# KQ_rfid_reader.net
KiCad netlist of a schematic drawn in EasyEDA
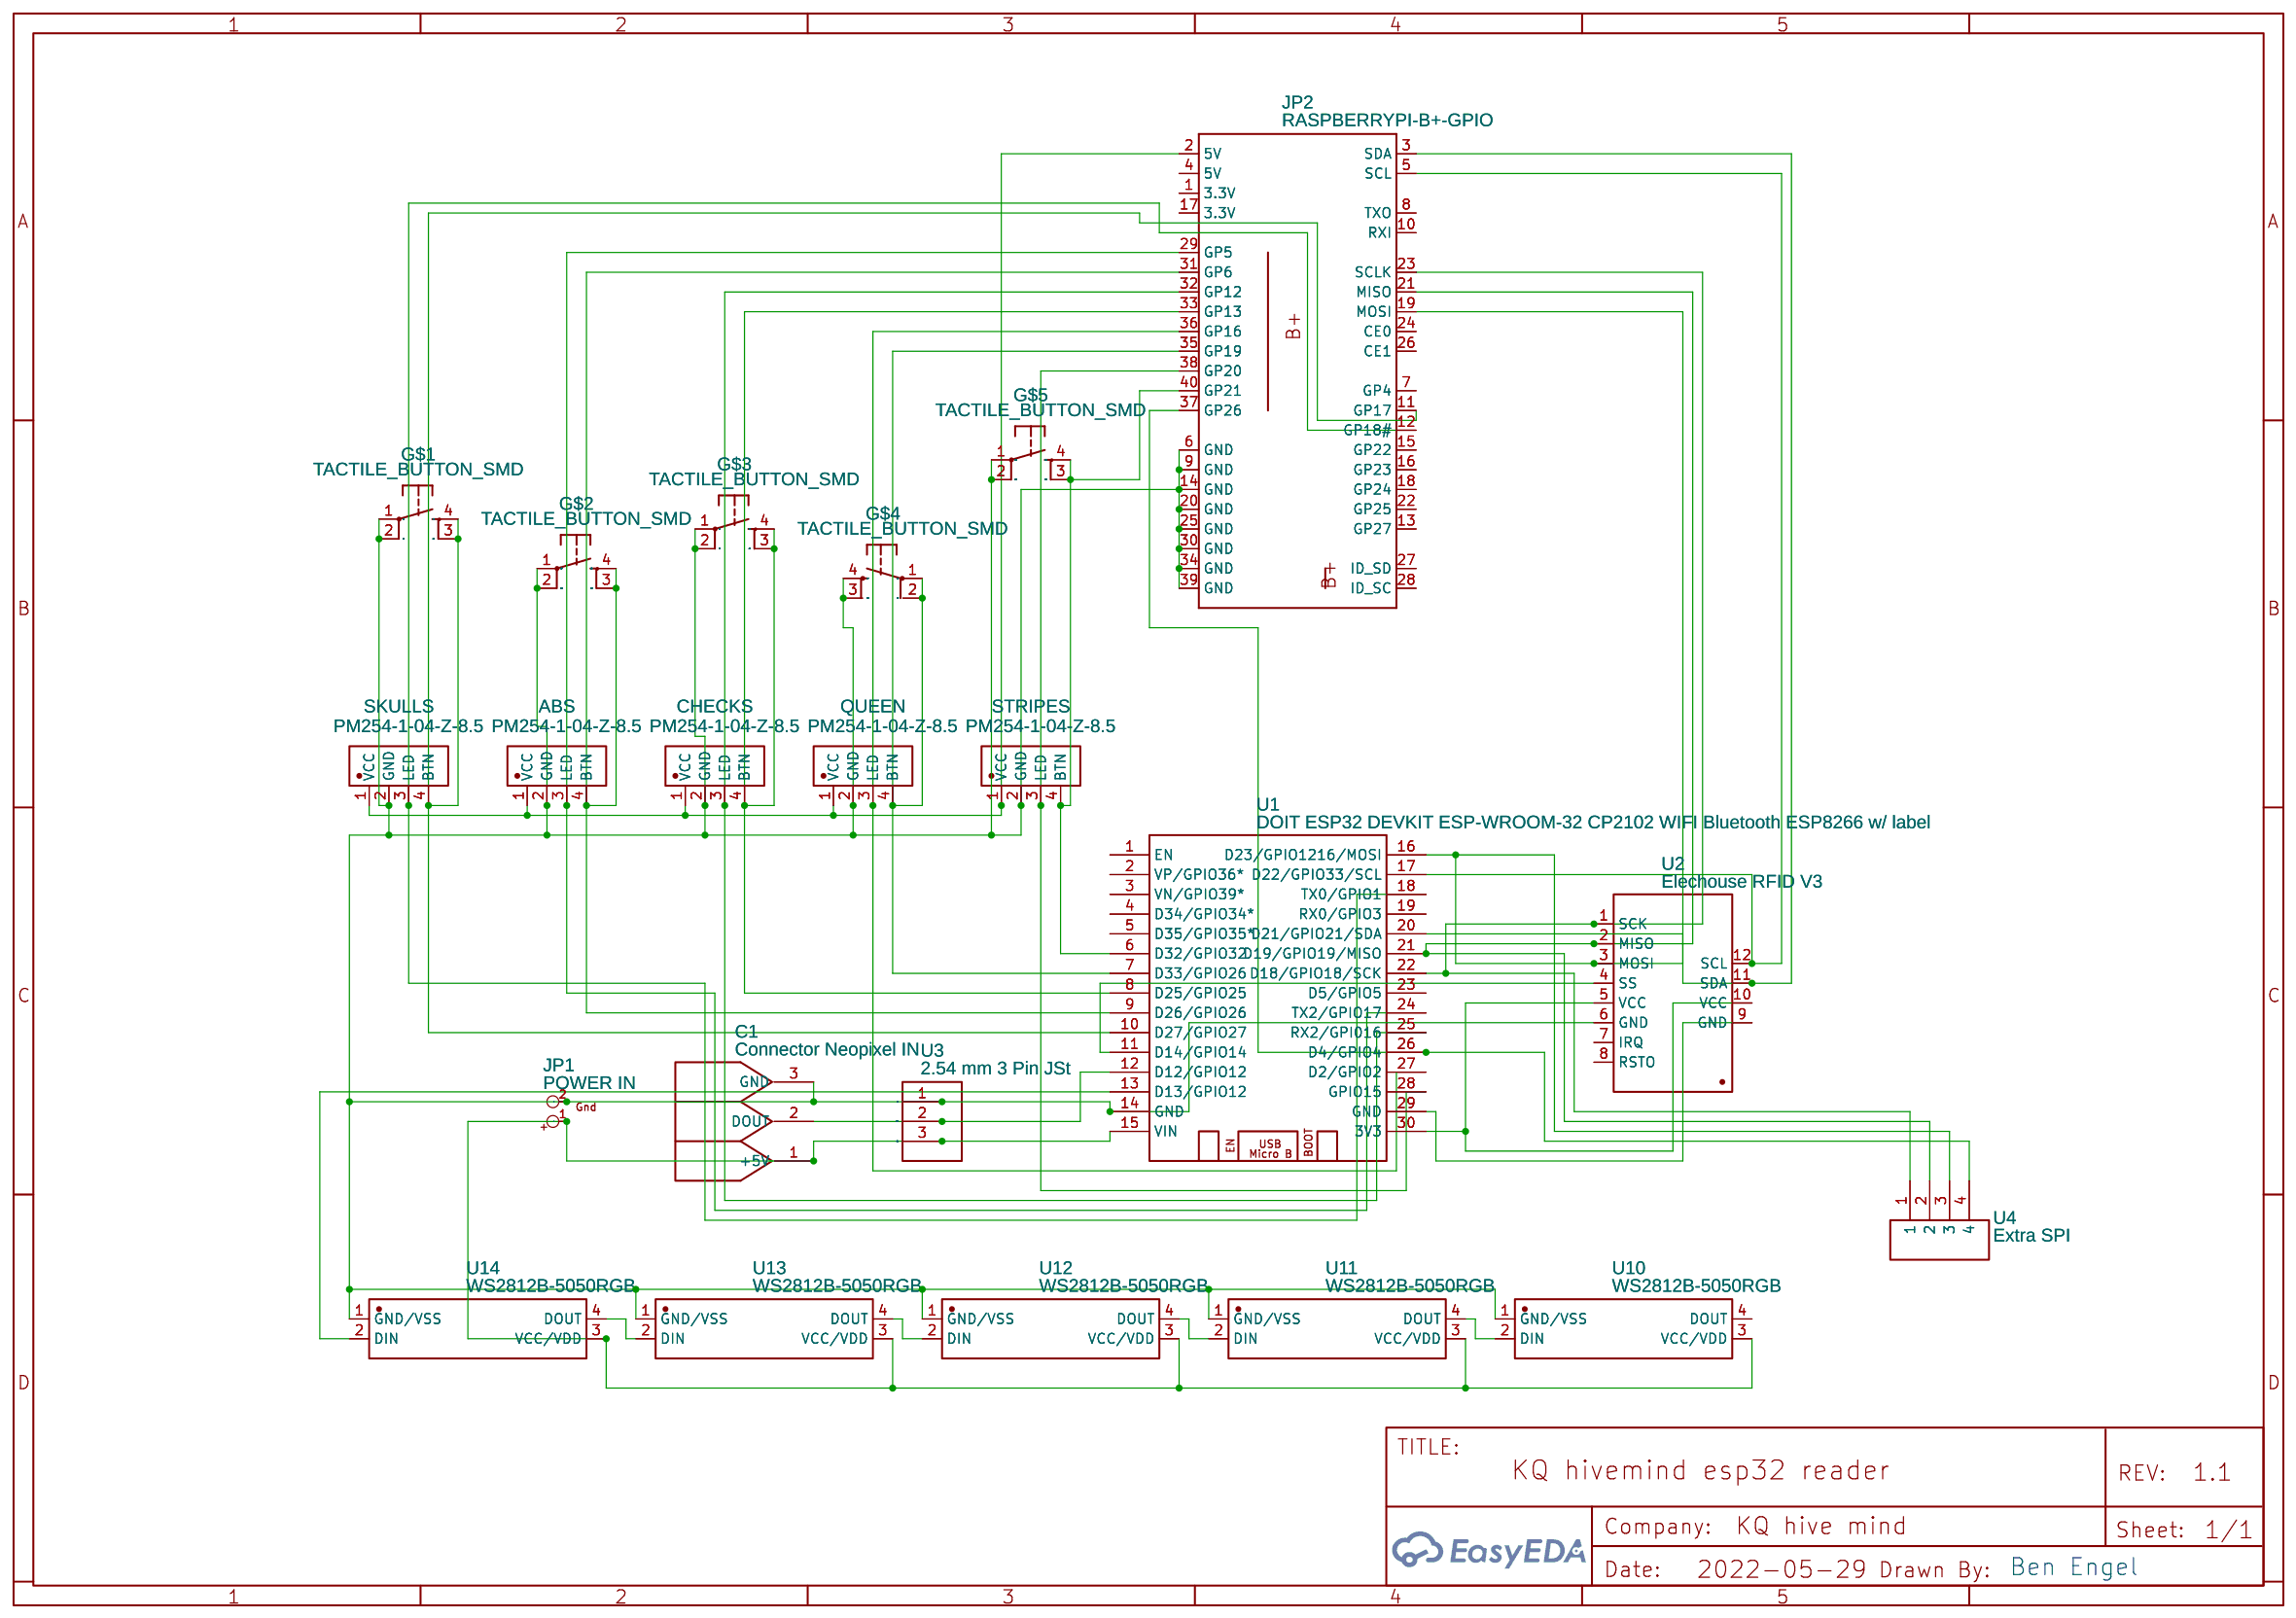
[diagram p0: schematic sheet]

(export (version "E")
  (design (tool "Eeschema 10.0.6"))
  (components
    (comp (ref "ABS")
      (value "PM254-1-04-Z-8.5")
      (fields (field (name "BOM_Supplier Part") "C2897367"))
      (libsource (lib "") (part "PM254-1-04-Z-8.5"))
    )
    (comp (ref "C1") (value "Connector Neopixel IN") (libsource (lib "") (part "Connector Neopixel IN")))
    (comp (ref "CHECKS")
      (value "PM254-1-04-Z-8.5")
      (fields (field (name "BOM_Supplier Part") "C2897367"))
      (libsource (lib "") (part "PM254-1-04-Z-8.5_1"))
    )
    (comp (ref "G$1") (value "TACTILE_BUTTON_SMD") (libsource (lib "") (part "TACTILE_BUTTON_SMD")))
    (comp (ref "G$2") (value "TACTILE_BUTTON_SMD") (libsource (lib "") (part "TACTILE_BUTTON_SMD")))
    (comp (ref "G$3") (value "TACTILE_BUTTON_SMD") (libsource (lib "") (part "TACTILE_BUTTON_SMD")))
    (comp (ref "G$4") (value "TACTILE_BUTTON_SMD") (libsource (lib "") (part "TACTILE_BUTTON_SMD_1")))
    (comp (ref "G$5") (value "TACTILE_BUTTON_SMD") (libsource (lib "") (part "TACTILE_BUTTON_SMD")))
    (comp (ref "JP1") (value "POWER IN") (libsource (lib "") (part "POWER IN")))
    (comp (ref "JP2") (value "RASPBERRYPI-B+-GPIO") (libsource (lib "") (part "RASPBERRYPI-B+-GPIO")))
    (comp (ref "QUEEN")
      (value "PM254-1-04-Z-8.5")
      (fields (field (name "BOM_Supplier Part") "C2897367"))
      (libsource (lib "") (part "PM254-1-04-Z-8.5_3"))
    )
    (comp (ref "SKULLS")
      (value "PM254-1-04-Z-8.5")
      (fields (field (name "BOM_Supplier Part") "C2897367"))
      (libsource (lib "") (part "PM254-1-04-Z-8.5_4"))
    )
    (comp (ref "STRIPES")
      (value "PM254-1-04-Z-8.5")
      (fields (field (name "BOM_Supplier Part") "C2897367"))
      (libsource (lib "") (part "PM254-1-04-Z-8.5_2"))
    )
    (comp (ref "U1")
      (value "DOIT ESP32 DEVKIT ESP-WROOM-32 CP2102 WIFI Bluetooth ESP8266 w/ label")
      (libsource (lib "") (part "DOIT ESP32 DEVKIT ESP-WROOM-32 CP2102 WIFI Bluetooth ESP8266 w/ label"))
    )
    (comp (ref "U2") (value "Elechouse RFID V3") (libsource (lib "") (part "Elechouse RFID V3")))
    (comp (ref "U3") (value "2.54 mm 3 Pin JSt") (libsource (lib "") (part "2.54 mm 3 Pin JSt")))
    (comp (ref "U4")
      (value "Extra SPI")
      (fields (field (name "BOM_Manufacturer Part") "1x2 Pin Header"))
      (libsource (lib "") (part "1X4 PIN HEADER"))
    )
    (comp (ref "U10")
      (value "WS2812B-5050RGB")
      (fields (field (name "BOM_Supplier Part") "C2838584"))
      (libsource (lib "") (part "WS2812B-5050RGB"))
    )
    (comp (ref "U11")
      (value "WS2812B-5050RGB")
      (fields (field (name "BOM_Supplier Part") "C2838584"))
      (libsource (lib "") (part "WS2812B-5050RGB"))
    )
    (comp (ref "U12")
      (value "WS2812B-5050RGB")
      (fields (field (name "BOM_Supplier Part") "C2838584"))
      (libsource (lib "") (part "WS2812B-5050RGB"))
    )
    (comp (ref "U13")
      (value "WS2812B-5050RGB")
      (fields (field (name "BOM_Supplier Part") "C2838584"))
      (libsource (lib "") (part "WS2812B-5050RGB"))
    )
    (comp (ref "U14")
      (value "WS2812B-5050RGB")
      (fields (field (name "BOM_Supplier Part") "C2838584"))
      (libsource (lib "") (part "WS2812B-5050RGB"))
    )
  )
  (nets
    (net (code "1") (name "Net-(ABS-BTN)") (class "Default")
      (node (ref "ABS") (pin "4") (pinfunction "BTN_4") (pintype "unspecified"))
      (node (ref "G$2") (pin "3") (pinfunction "SWB2_3") (pintype "bidirectional"))
      (node (ref "G$2") (pin "4") (pinfunction "SWA2_4") (pintype "bidirectional"))
      (node (ref "JP2") (pin "31") (pinfunction "GP6_31") (pintype "unspecified"))
      (node (ref "U1") (pin "9") (pinfunction "D26/GPIO26_9") (pintype "bidirectional"))
    )
    (net (code "2") (name "Net-(ABS-GND)") (class "Default")
      (node (ref "ABS") (pin "2") (pinfunction "GND_2") (pintype "unspecified"))
      (node (ref "C1") (pin "3") (pinfunction "GND_3") (pintype "unspecified"))
      (node (ref "CHECKS") (pin "2") (pinfunction "GND_2") (pintype "unspecified"))
      (node (ref "G$1") (pin "1") (pinfunction "SWA1_1") (pintype "bidirectional"))
      (node (ref "G$1") (pin "2") (pinfunction "SWB1_2") (pintype "bidirectional"))
      (node (ref "G$2") (pin "1") (pinfunction "SWA1_1") (pintype "bidirectional"))
      (node (ref "G$2") (pin "2") (pinfunction "SWB1_2") (pintype "bidirectional"))
      (node (ref "G$3") (pin "1") (pinfunction "SWA1_1") (pintype "bidirectional"))
      (node (ref "G$3") (pin "2") (pinfunction "SWB1_2") (pintype "bidirectional"))
      (node (ref "G$4") (pin "3") (pinfunction "SWB2_3") (pintype "bidirectional"))
      (node (ref "G$4") (pin "4") (pinfunction "SWA2_4") (pintype "bidirectional"))
      (node (ref "G$5") (pin "1") (pinfunction "SWA1_1") (pintype "bidirectional"))
      (node (ref "G$5") (pin "2") (pinfunction "SWB1_2") (pintype "bidirectional"))
      (node (ref "JP1") (pin "2") (pinfunction "-_2") (pintype "unspecified"))
      (node (ref "JP2") (pin "14") (pinfunction "GND_14") (pintype "passive"))
      (node (ref "JP2") (pin "20") (pinfunction "GND_20") (pintype "passive"))
      (node (ref "JP2") (pin "25") (pinfunction "GND_25") (pintype "passive"))
      (node (ref "JP2") (pin "30") (pinfunction "GND_30") (pintype "passive"))
      (node (ref "JP2") (pin "34") (pinfunction "GND_34") (pintype "passive"))
      (node (ref "JP2") (pin "39") (pinfunction "GND_39") (pintype "passive"))
      (node (ref "JP2") (pin "6") (pinfunction "GND_6") (pintype "passive"))
      (node (ref "JP2") (pin "9") (pinfunction "GND_9") (pintype "passive"))
      (node (ref "QUEEN") (pin "2") (pinfunction "GND_2") (pintype "unspecified"))
      (node (ref "SKULLS") (pin "2") (pinfunction "GND_2") (pintype "unspecified"))
      (node (ref "STRIPES") (pin "2") (pinfunction "GND_2") (pintype "unspecified"))
      (node (ref "U1") (pin "14") (pinfunction "GND_14") (pintype "bidirectional"))
      (node (ref "U10") (pin "1") (pinfunction "GND/VSS_1") (pintype "unspecified"))
      (node (ref "U11") (pin "1") (pinfunction "GND/VSS_1") (pintype "unspecified"))
      (node (ref "U12") (pin "1") (pinfunction "GND/VSS_1") (pintype "unspecified"))
      (node (ref "U13") (pin "1") (pinfunction "GND/VSS_1") (pintype "unspecified"))
      (node (ref "U14") (pin "1") (pinfunction "GND/VSS_1") (pintype "unspecified"))
      (node (ref "U2") (pin "6") (pinfunction "GND_6") (pintype "unspecified"))
      (node (ref "U3") (pin "1") (pinfunction "PIN_1") (pintype "unspecified"))
    )
    (net (code "3") (name "Net-(ABS-LED)") (class "Default")
      (node (ref "ABS") (pin "3") (pinfunction "LED_3") (pintype "unspecified"))
      (node (ref "JP2") (pin "29") (pinfunction "GP5_29") (pintype "unspecified"))
      (node (ref "U1") (pin "24") (pinfunction "TX2/GPIO17_24") (pintype "bidirectional"))
    )
    (net (code "4") (name "Net-(ABS-VCC)") (class "Default")
      (node (ref "ABS") (pin "1") (pinfunction "VCC_1") (pintype "unspecified"))
      (node (ref "CHECKS") (pin "1") (pinfunction "VCC_1") (pintype "unspecified"))
      (node (ref "JP2") (pin "2") (pinfunction "5V_2") (pintype "passive"))
      (node (ref "QUEEN") (pin "1") (pinfunction "VCC_1") (pintype "unspecified"))
      (node (ref "SKULLS") (pin "1") (pinfunction "VCC_1") (pintype "unspecified"))
      (node (ref "STRIPES") (pin "1") (pinfunction "VCC_1") (pintype "unspecified"))
    )
    (net (code "5") (name "Net-(C1-+5V)") (class "Default")
      (node (ref "C1") (pin "1") (pinfunction "+5V_1") (pintype "unspecified"))
      (node (ref "JP1") (pin "1") (pinfunction "+_1") (pintype "unspecified"))
      (node (ref "U1") (pin "15") (pinfunction "VIN_15") (pintype "input"))
      (node (ref "U10") (pin "3") (pinfunction "VCC/VDD_3") (pintype "unspecified"))
      (node (ref "U11") (pin "3") (pinfunction "VCC/VDD_3") (pintype "unspecified"))
      (node (ref "U12") (pin "3") (pinfunction "VCC/VDD_3") (pintype "unspecified"))
      (node (ref "U13") (pin "3") (pinfunction "VCC/VDD_3") (pintype "unspecified"))
      (node (ref "U14") (pin "3") (pinfunction "VCC/VDD_3") (pintype "unspecified"))
      (node (ref "U3") (pin "3") (pinfunction "OUTER_3") (pintype "unspecified"))
    )
    (net (code "6") (name "Net-(C1-DOUT)") (class "Default")
      (node (ref "C1") (pin "2") (pinfunction "DOUT_2") (pintype "unspecified"))
      (node (ref "U1") (pin "12") (pinfunction "D12/GPIO12_12") (pintype "bidirectional"))
      (node (ref "U3") (pin "2") (pinfunction "SWITCH_2") (pintype "unspecified"))
    )
    (net (code "7") (name "Net-(CHECKS-BTN)") (class "Default")
      (node (ref "CHECKS") (pin "4") (pinfunction "BTN_4") (pintype "unspecified"))
      (node (ref "G$3") (pin "3") (pinfunction "SWB2_3") (pintype "bidirectional"))
      (node (ref "G$3") (pin "4") (pinfunction "SWA2_4") (pintype "bidirectional"))
      (node (ref "JP2") (pin "33") (pinfunction "GP13_33") (pintype "unspecified"))
      (node (ref "U1") (pin "8") (pinfunction "D25/GPIO25_8") (pintype "bidirectional"))
    )
    (net (code "8") (name "Net-(CHECKS-LED)") (class "Default")
      (node (ref "CHECKS") (pin "3") (pinfunction "LED_3") (pintype "unspecified"))
      (node (ref "JP2") (pin "32") (pinfunction "GP12_32") (pintype "unspecified"))
      (node (ref "U1") (pin "25") (pinfunction "RX2/GPI016_25") (pintype "bidirectional"))
    )
    (net (code "9") (name "Net-(G$1-SWA2)") (class "Default")
      (node (ref "G$1") (pin "3") (pinfunction "SWB2_3") (pintype "bidirectional"))
      (node (ref "G$1") (pin "4") (pinfunction "SWA2_4") (pintype "bidirectional"))
      (node (ref "JP2") (pin "11") (pinfunction "GP17_11") (pintype "unspecified"))
      (node (ref "SKULLS") (pin "4") (pinfunction "BTN_4") (pintype "unspecified"))
      (node (ref "U1") (pin "10") (pinfunction "D27/GPIO27_10") (pintype "bidirectional"))
    )
    (net (code "10") (name "Net-(G$4-SWA1)") (class "Default")
      (node (ref "G$4") (pin "1") (pinfunction "SWA1_1") (pintype "bidirectional"))
      (node (ref "G$4") (pin "2") (pinfunction "SWB1_2") (pintype "bidirectional"))
      (node (ref "JP2") (pin "35") (pinfunction "GP19_35") (pintype "unspecified"))
      (node (ref "QUEEN") (pin "4") (pinfunction "BTN_4") (pintype "unspecified"))
      (node (ref "U1") (pin "7") (pinfunction "D33/GPIO26_7") (pintype "bidirectional"))
    )
    (net (code "11") (name "Net-(G$5-SWA2)") (class "Default")
      (node (ref "G$5") (pin "3") (pinfunction "SWB2_3") (pintype "bidirectional"))
      (node (ref "G$5") (pin "4") (pinfunction "SWA2_4") (pintype "bidirectional"))
      (node (ref "JP2") (pin "40") (pinfunction "GP21_40") (pintype "unspecified"))
      (node (ref "STRIPES") (pin "4") (pinfunction "BTN_4") (pintype "unspecified"))
      (node (ref "U1") (pin "6") (pinfunction "D32/GPIO32_6") (pintype "bidirectional"))
    )
    (net (code "12") (name "Net-(JP2-GP16)") (class "Default")
      (node (ref "JP2") (pin "36") (pinfunction "GP16_36") (pintype "unspecified"))
      (node (ref "QUEEN") (pin "3") (pinfunction "LED_3") (pintype "unspecified"))
      (node (ref "U1") (pin "27") (pinfunction "D2/GPIO2_27") (pintype "bidirectional"))
    )
    (net (code "13") (name "Net-(JP2-GP18#)") (class "Default")
      (node (ref "JP2") (pin "12") (pinfunction "GP18#_12") (pintype "unspecified"))
      (node (ref "SKULLS") (pin "3") (pinfunction "LED_3") (pintype "unspecified"))
      (node (ref "U1") (pin "18") (pinfunction "TX0/GPIO1_18") (pintype "bidirectional"))
    )
    (net (code "14") (name "Net-(JP2-GP20)") (class "Default")
      (node (ref "JP2") (pin "38") (pinfunction "GP20_38") (pintype "unspecified"))
      (node (ref "STRIPES") (pin "3") (pinfunction "LED_3") (pintype "unspecified"))
      (node (ref "U1") (pin "28") (pinfunction "GPIO15_28") (pintype "bidirectional"))
    )
    (net (code "15") (name "Net-(JP2-GP26)") (class "Default")
      (node (ref "JP2") (pin "37") (pinfunction "GP26_37") (pintype "unspecified"))
      (node (ref "U1") (pin "26") (pinfunction "D4/GPIO4_26") (pintype "bidirectional"))
      (node (ref "U4") (pin "4") (pinfunction "4_4") (pintype "unspecified"))
    )
    (net (code "16") (name "Net-(JP2-MISO)") (class "Default")
      (node (ref "JP2") (pin "21") (pinfunction "MISO_21") (pintype "input"))
      (node (ref "U1") (pin "21") (pinfunction "D19/GPIO19/MISO_21") (pintype "bidirectional"))
      (node (ref "U2") (pin "2") (pinfunction "MISO_2") (pintype "unspecified"))
      (node (ref "U4") (pin "2") (pinfunction "2_2") (pintype "unspecified"))
    )
    (net (code "17") (name "Net-(JP2-MOSI)") (class "Default")
      (node (ref "JP2") (pin "19") (pinfunction "MOSI_19") (pintype "output"))
      (node (ref "U1") (pin "16") (pinfunction "D23/GPIO1216/MOSI_16") (pintype "bidirectional"))
      (node (ref "U2") (pin "3") (pinfunction "MOSI_3") (pintype "unspecified"))
      (node (ref "U4") (pin "3") (pinfunction "3_3") (pintype "unspecified"))
    )
    (net (code "18") (name "Net-(JP2-SCL)") (class "Default")
      (node (ref "JP2") (pin "5") (pinfunction "SCL_5") (pintype "unspecified"))
      (node (ref "U1") (pin "17") (pinfunction "D22/GPIO33/SCL_17") (pintype "bidirectional"))
      (node (ref "U2") (pin "12") (pinfunction "SCL_12") (pintype "unspecified"))
    )
    (net (code "19") (name "Net-(JP2-SCLK)") (class "Default")
      (node (ref "JP2") (pin "23") (pinfunction "SCLK_23") (pintype "output"))
      (node (ref "U1") (pin "22") (pinfunction "D18/GPIO18/SCK_22") (pintype "bidirectional"))
      (node (ref "U2") (pin "1") (pinfunction "SCK_1") (pintype "unspecified"))
      (node (ref "U4") (pin "1") (pinfunction "1_1") (pintype "unspecified"))
    )
    (net (code "20") (name "Net-(JP2-SDA)") (class "Default")
      (node (ref "JP2") (pin "3") (pinfunction "SDA_3") (pintype "unspecified"))
      (node (ref "U1") (pin "20") (pinfunction "D21/GPIO21/SDA_20") (pintype "bidirectional"))
      (node (ref "U2") (pin "11") (pinfunction "SDA_11") (pintype "unspecified"))
    )
    (net (code "21") (name "Net-(U1-3V3)") (class "Default")
      (node (ref "U1") (pin "30") (pinfunction "3V3_30") (pintype "bidirectional"))
      (node (ref "U2") (pin "10") (pinfunction "VCC_10") (pintype "unspecified"))
      (node (ref "U2") (pin "5") (pinfunction "VCC_5") (pintype "unspecified"))
    )
    (net (code "22") (name "Net-(U1-D13{slash}GPIO12)") (class "Default")
      (node (ref "U1") (pin "13") (pinfunction "D13/GPIO12_13") (pintype "bidirectional"))
      (node (ref "U14") (pin "2") (pinfunction "DIN_2") (pintype "unspecified"))
    )
    (net (code "23") (name "Net-(U1-D14{slash}GPIO14)") (class "Default")
      (node (ref "U1") (pin "11") (pinfunction "D14/GPIO14_11") (pintype "bidirectional"))
      (node (ref "U2") (pin "4") (pinfunction "SS_4") (pintype "unspecified"))
    )
    (net (code "24") (name "Net-(U1-GND-Pad29)") (class "Default")
      (node (ref "U1") (pin "29") (pinfunction "GND_29") (pintype "bidirectional"))
      (node (ref "U2") (pin "9") (pinfunction "GND_9") (pintype "unspecified"))
    )
    (net (code "25") (name "Net-(U10-DIN)") (class "Default")
      (node (ref "U10") (pin "2") (pinfunction "DIN_2") (pintype "unspecified"))
      (node (ref "U11") (pin "4") (pinfunction "DOUT_4") (pintype "unspecified"))
    )
    (net (code "26") (name "Net-(U11-DIN)") (class "Default")
      (node (ref "U11") (pin "2") (pinfunction "DIN_2") (pintype "unspecified"))
      (node (ref "U12") (pin "4") (pinfunction "DOUT_4") (pintype "unspecified"))
    )
    (net (code "27") (name "Net-(U12-DIN)") (class "Default")
      (node (ref "U12") (pin "2") (pinfunction "DIN_2") (pintype "unspecified"))
      (node (ref "U13") (pin "4") (pinfunction "DOUT_4") (pintype "unspecified"))
    )
    (net (code "28") (name "Net-(U13-DIN)") (class "Default")
      (node (ref "U13") (pin "2") (pinfunction "DIN_2") (pintype "unspecified"))
      (node (ref "U14") (pin "4") (pinfunction "DOUT_4") (pintype "unspecified"))
    )
    (net (code "29") (name "unconnected-(JP2-3.3V-Pad1)") (class "Default")
      (node (ref "JP2") (pin "1") (pinfunction "3.3V_1") (pintype "passive"))
    )
    (net (code "30") (name "unconnected-(JP2-3.3V-Pad17)") (class "Default")
      (node (ref "JP2") (pin "17") (pinfunction "3.3V_17") (pintype "passive"))
    )
    (net (code "31") (name "unconnected-(JP2-5V-Pad4)") (class "Default")
      (node (ref "JP2") (pin "4") (pinfunction "5V_4") (pintype "passive"))
    )
    (net (code "32") (name "unconnected-(JP2-CE0-Pad24)") (class "Default")
      (node (ref "JP2") (pin "24") (pinfunction "CE0_24") (pintype "output"))
    )
    (net (code "33") (name "unconnected-(JP2-CE1-Pad26)") (class "Default")
      (node (ref "JP2") (pin "26") (pinfunction "CE1_26") (pintype "output"))
    )
    (net (code "34") (name "unconnected-(JP2-GP4-Pad7)") (class "Default")
      (node (ref "JP2") (pin "7") (pinfunction "GP4_7") (pintype "unspecified"))
    )
    (net (code "35") (name "unconnected-(JP2-GP22-Pad15)") (class "Default")
      (node (ref "JP2") (pin "15") (pinfunction "GP22_15") (pintype "unspecified"))
    )
    (net (code "36") (name "unconnected-(JP2-GP23-Pad16)") (class "Default")
      (node (ref "JP2") (pin "16") (pinfunction "GP23_16") (pintype "unspecified"))
    )
    (net (code "37") (name "unconnected-(JP2-GP24-Pad18)") (class "Default")
      (node (ref "JP2") (pin "18") (pinfunction "GP24_18") (pintype "unspecified"))
    )
    (net (code "38") (name "unconnected-(JP2-GP25-Pad22)") (class "Default")
      (node (ref "JP2") (pin "22") (pinfunction "GP25_22") (pintype "unspecified"))
    )
    (net (code "39") (name "unconnected-(JP2-GP27-Pad13)") (class "Default")
      (node (ref "JP2") (pin "13") (pinfunction "GP27_13") (pintype "unspecified"))
    )
    (net (code "40") (name "unconnected-(JP2-ID_SC-Pad28)") (class "Default")
      (node (ref "JP2") (pin "28") (pinfunction "ID_SC_28") (pintype "unspecified"))
    )
    (net (code "41") (name "unconnected-(JP2-ID_SD-Pad27)") (class "Default")
      (node (ref "JP2") (pin "27") (pinfunction "ID_SD_27") (pintype "unspecified"))
    )
    (net (code "42") (name "unconnected-(JP2-RXI-Pad10)") (class "Default")
      (node (ref "JP2") (pin "10") (pinfunction "RXI_10") (pintype "input"))
    )
    (net (code "43") (name "unconnected-(JP2-TXO-Pad8)") (class "Default")
      (node (ref "JP2") (pin "8") (pinfunction "TXO_8") (pintype "output"))
    )
    (net (code "44") (name "unconnected-(U1-D5{slash}GPIO5-Pad23)") (class "Default")
      (node (ref "U1") (pin "23") (pinfunction "D5/GPIO5_23") (pintype "bidirectional"))
    )
    (net (code "45") (name "unconnected-(U1-D34{slash}GPIO34*-Pad4)") (class "Default")
      (node (ref "U1") (pin "4") (pinfunction "D34/GPIO34*_4") (pintype "input"))
    )
    (net (code "46") (name "unconnected-(U1-D35{slash}GPIO35*-Pad5)") (class "Default")
      (node (ref "U1") (pin "5") (pinfunction "D35/GPIO35*_5") (pintype "input"))
    )
    (net (code "47") (name "unconnected-(U1-EN-Pad1)") (class "Default")
      (node (ref "U1") (pin "1") (pinfunction "EN_1") (pintype "bidirectional"))
    )
    (net (code "48") (name "unconnected-(U1-RX0{slash}GPIO3-Pad19)") (class "Default")
      (node (ref "U1") (pin "19") (pinfunction "RX0/GPIO3_19") (pintype "bidirectional"))
    )
    (net (code "49") (name "unconnected-(U1-VN{slash}GPIO39*-Pad3)") (class "Default")
      (node (ref "U1") (pin "3") (pinfunction "VN/GPIO39*_3") (pintype "input"))
    )
    (net (code "50") (name "unconnected-(U1-VP{slash}GPIO36*-Pad2)") (class "Default")
      (node (ref "U1") (pin "2") (pinfunction "VP/GPIO36*_2") (pintype "input"))
    )
    (net (code "51") (name "unconnected-(U2-IRQ-Pad7)") (class "Default")
      (node (ref "U2") (pin "7") (pinfunction "IRQ_7") (pintype "unspecified"))
    )
    (net (code "52") (name "unconnected-(U2-RSTO-Pad8)") (class "Default")
      (node (ref "U2") (pin "8") (pinfunction "RSTO_8") (pintype "unspecified"))
    )
    (net (code "53") (name "unconnected-(U10-DOUT-Pad4)") (class "Default")
      (node (ref "U10") (pin "4") (pinfunction "DOUT_4") (pintype "unspecified"))
    )
  )
)
